# MGT.net
KiCad netlist of a schematic drawn in Altium Designer
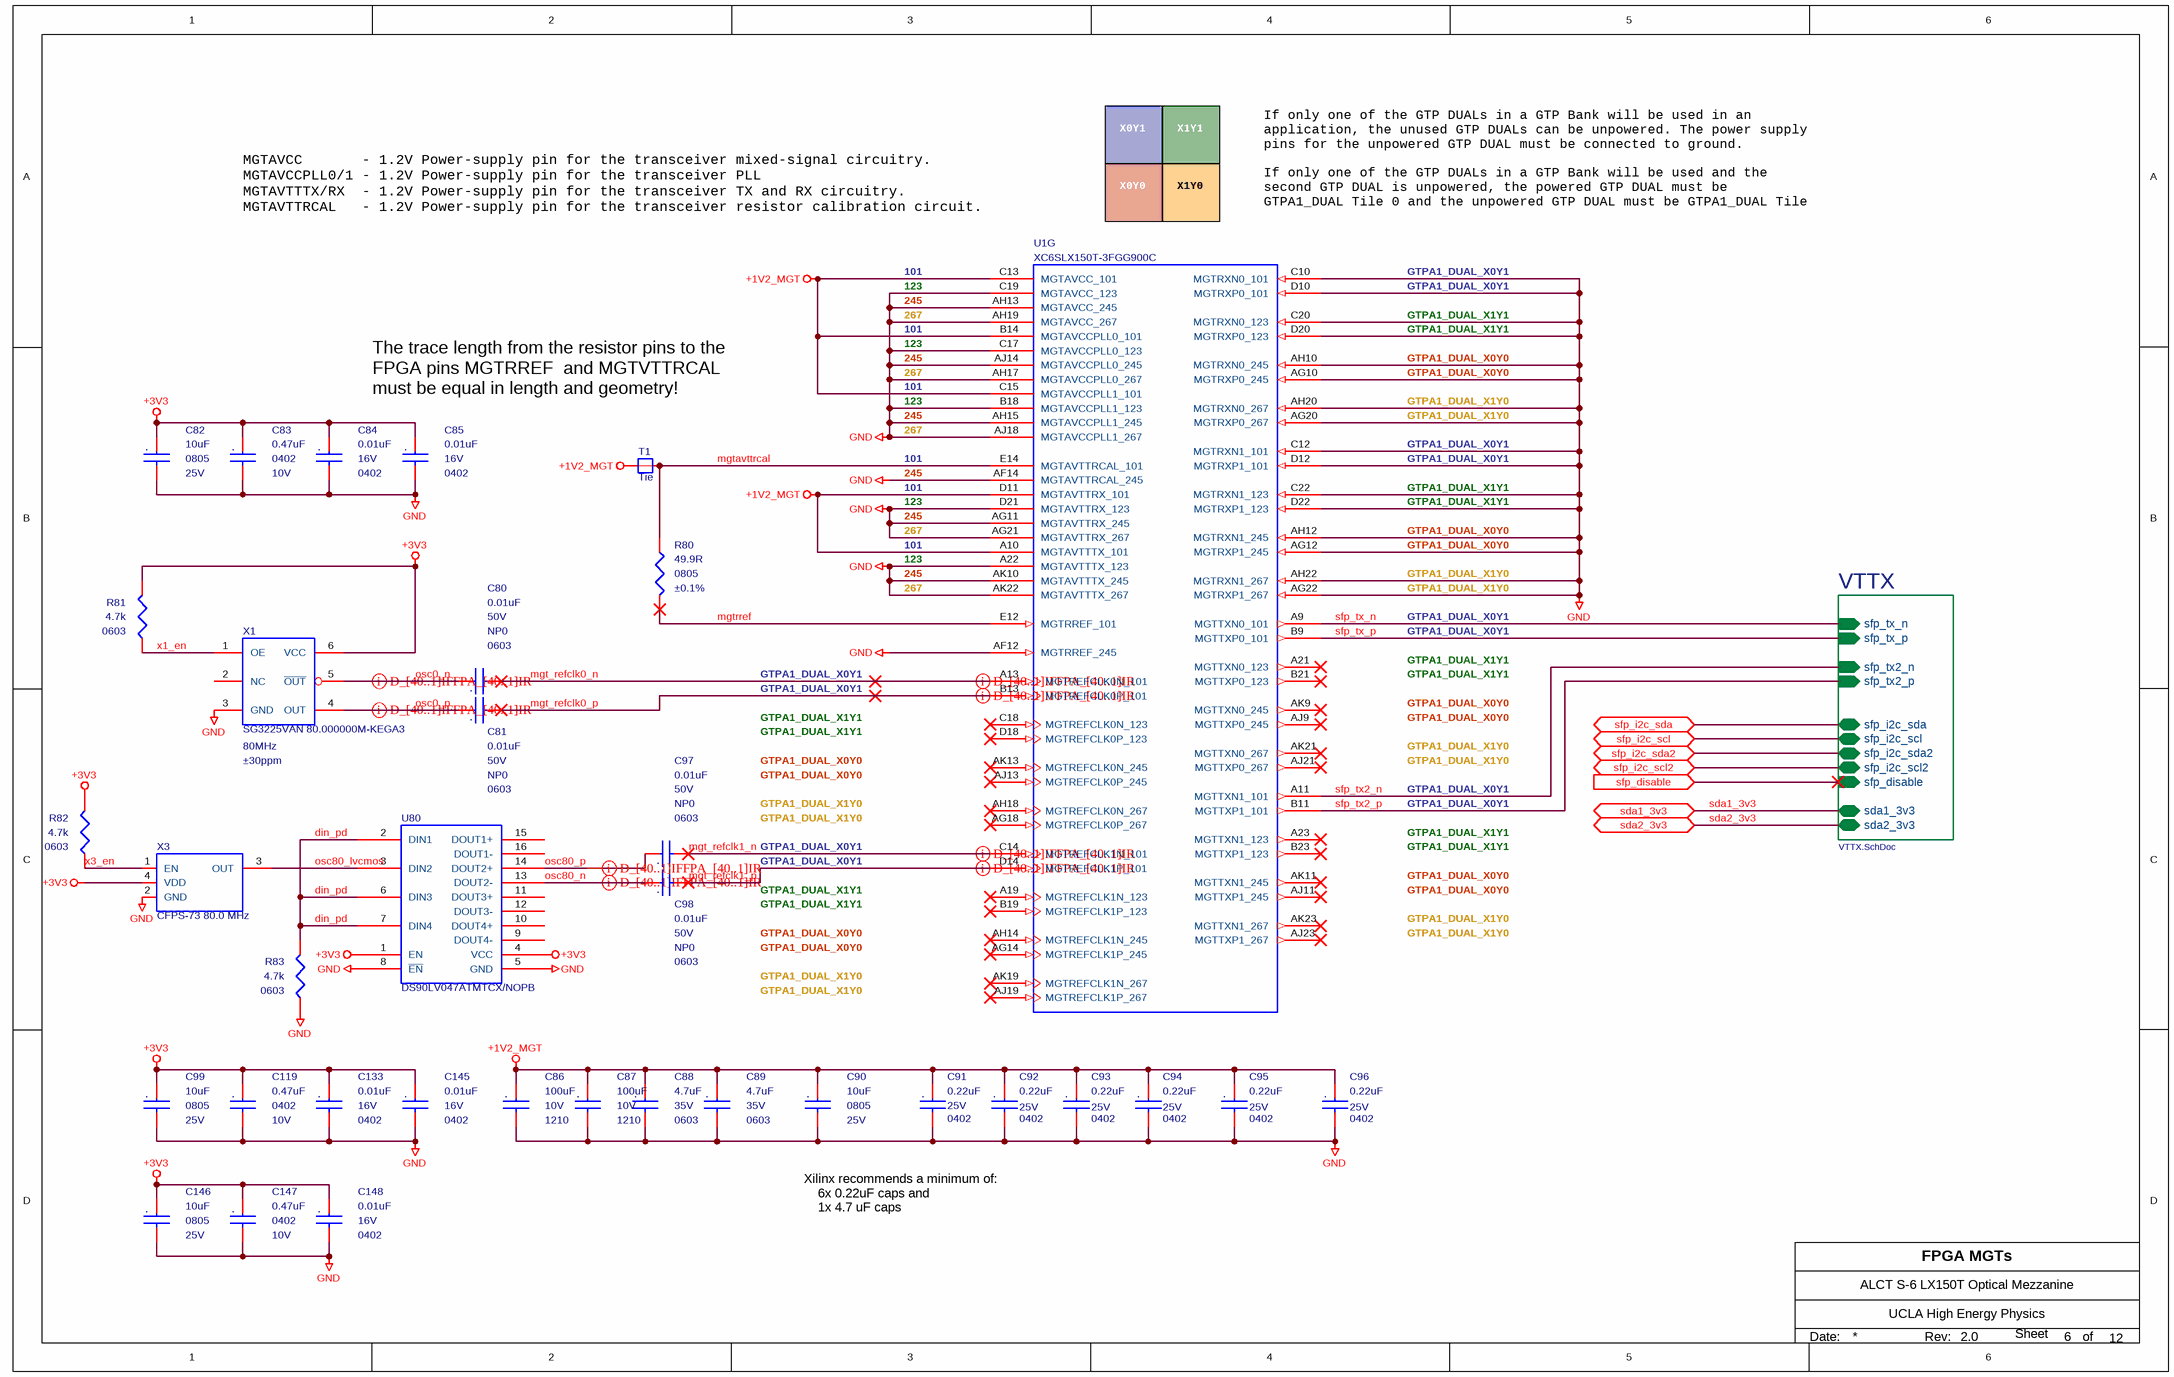
[diagram p0: MGT.SchDoc]

(export (version "E")
  (design (tool "Eeschema 10.0.6"))
  (components
    (comp (ref "C80")
      (value "0.01uF")
      (footprint "MC_S6/SM/C_0603_IPC")
      (description "CAP CER 10000PF 50V NP0 0603")
      (fields
        (field (name "MANUFACTURER") "KEMET")
        (field (name "MANUFACTURER PART NUMBER") "C0603C103J3GACTU")
        (field (name "TEMPERATURE COEFFICIENT") "NP0")
        (field (name "PACKAGE") "0603")
        (field (name "VOLTAGE - RATED") "50V")
      )
      (libsource (lib "ALCT_MEZ_SPARTAN6_Library") (part "C0603C103J3GACTU"))
    )
    (comp (ref "C81")
      (value "0.01uF")
      (footprint "MC_S6/SM/C_0603_IPC")
      (description "CAP CER 10000PF 50V NP0 0603")
      (fields
        (field (name "MANUFACTURER") "KEMET")
        (field (name "MANUFACTURER PART NUMBER") "C0603C103J3GACTU")
        (field (name "TEMPERATURE COEFFICIENT") "NP0")
        (field (name "PACKAGE") "0603")
        (field (name "VOLTAGE - RATED") "50V")
      )
      (libsource (lib "ALCT_MEZ_SPARTAN6_Library") (part "C0603C103J3GACTU"))
    )
    (comp (ref "C82")
      (value "10uF")
      (footprint "MC_S6/SM/C_0805_IPC")
      (description "CAP CER 10UF 25V X5R 0805")
      (fields
        (field (name "MANUFACTURER") "Murata Electronics North America")
        (field (name "MANUFACTURER PART NUMBER") "GRM21BR61E106KA73L")
        (field (name "VOLTAGE - RATED") "25V")
        (field (name "PACKAGE") "0805")
      )
      (libsource (lib "ALCT_MEZ_SPARTAN6_Library") (part "GRM21BR61E106KA73L"))
    )
    (comp (ref "C83")
      (value "0.47uF")
      (footprint "MC_S6/SM/C_0402_IPC")
      (description "CAP CER 0.47UF 10V X5R 0402")
      (fields
        (field (name "MANUFACTURER") "Murata Electronics North America")
        (field (name "MANUFACTURER PART NUMBER") "GRM155R61A474KE15J")
        (field (name "VOLTAGE - RATED") "10V")
        (field (name "PACKAGE") "0402")
      )
      (libsource (lib "ALCT_MEZ_SPARTAN6_Library") (part "GRM155R61A474KE15J"))
    )
    (comp (ref "C84")
      (value "0.01uF")
      (footprint "MC_S6/SM/C_0402_IPC")
      (description "CAP CER 10nF 16V X7R 0402")
      (fields
        (field (name "MANUFACTURER") "KEMET")
        (field (name "MANUFACTURER PART NUMBER") "C0402C103K4RACTU")
        (field (name "VOLTAGE - RATED") "16V")
        (field (name "PACKAGE") "0402")
      )
      (libsource (lib "ALCT_MEZ_SPARTAN6_Library") (part "C0402C103K4RACTU"))
    )
    (comp (ref "C85")
      (value "0.01uF")
      (footprint "MC_S6/SM/C_0402_IPC")
      (description "CAP CER 10nF 16V X7R 0402")
      (fields
        (field (name "MANUFACTURER") "KEMET")
        (field (name "MANUFACTURER PART NUMBER") "C0402C103K4RACTU")
        (field (name "VOLTAGE - RATED") "16V")
        (field (name "PACKAGE") "0402")
      )
      (libsource (lib "ALCT_MEZ_SPARTAN6_Library") (part "C0402C103K4RACTU"))
    )
    (comp (ref "C86")
      (value "100uF")
      (footprint "MC_S6/SM/C_1210_IPC")
      (description "CAP CER 100UF 10V X5R 1210")
      (fields
        (field (name "MANUFACTURER") "Taiyo Yuden")
        (field (name "MANUFACTURER PART NUMBER") "LMK325BJ107MM-T")
        (field (name "VOLTAGE - RATED") "10V")
        (field (name "PACKAGE") "1210")
      )
      (libsource (lib "ALCT_MEZ_SPARTAN6_Library") (part "LMK325BJ107MM-T"))
    )
    (comp (ref "C87")
      (value "100uF")
      (footprint "MC_S6/SM/C_1210_IPC")
      (description "CAP CER 100UF 10V X5R 1210")
      (fields
        (field (name "MANUFACTURER") "Taiyo Yuden")
        (field (name "MANUFACTURER PART NUMBER") "LMK325BJ107MM-T")
        (field (name "VOLTAGE - RATED") "10V")
        (field (name "PACKAGE") "1210")
      )
      (libsource (lib "ALCT_MEZ_SPARTAN6_Library") (part "LMK325BJ107MM-T"))
    )
    (comp (ref "C88")
      (value "4.7uF")
      (footprint "MC_S6/SM/C_0603_IPC")
      (description "CAP CER 4.7UF 35V X5R 0603")
      (fields
        (field (name "MANUFACTURER") "Murata")
        (field (name "MANUFACTURER PART NUMBER") "GRM188R6YA475KE15D")
        (field (name "VOLTAGE - RATED") "35V")
        (field (name "PACKAGE") "0603")
      )
      (libsource (lib "ALCT_MEZ_SPARTAN6_Library") (part "GRM188R6YA475KE15D"))
    )
    (comp (ref "C89")
      (value "4.7uF")
      (footprint "MC_S6/SM/C_0603_IPC")
      (description "CAP CER 4.7UF 35V X5R 0603")
      (fields
        (field (name "MANUFACTURER") "Murata")
        (field (name "MANUFACTURER PART NUMBER") "GRM188R6YA475KE15D")
        (field (name "VOLTAGE - RATED") "35V")
        (field (name "PACKAGE") "0603")
      )
      (libsource (lib "ALCT_MEZ_SPARTAN6_Library") (part "GRM188R6YA475KE15D"))
    )
    (comp (ref "C90")
      (value "10uF")
      (footprint "MC_S6/SM/C_0805_IPC")
      (description "CAP CER 10UF 25V X5R 0805")
      (fields
        (field (name "MANUFACTURER") "Murata Electronics North America")
        (field (name "MANUFACTURER PART NUMBER") "GRM21BR61E106KA73L")
        (field (name "VOLTAGE - RATED") "25V")
        (field (name "PACKAGE") "0805")
      )
      (libsource (lib "ALCT_MEZ_SPARTAN6_Library") (part "GRM21BR61E106KA73L"))
    )
    (comp (ref "C91")
      (value "0.22uF")
      (footprint "MC_S6/SM/C_0402_IPC")
      (description "CAP CER 0.22UF 15V X7R 0402")
      (fields
        (field (name "MANUFACTURER") "Murata Electronics North America")
        (field (name "MANUFACTURER PART NUMBER") "GRM155R71C224KA12D")
        (field (name "VOLTAGE - RATED") "25V")
        (field (name "PACKAGE") "0402")
      )
      (libsource (lib "ALCT_MEZ_SPARTAN6_Library") (part "GRM155R71C224KA12D"))
    )
    (comp (ref "C92")
      (value "0.22uF")
      (footprint "MC_S6/SM/C_0402_IPC")
      (description "CAP CER 0.22UF 15V X7R 0402")
      (fields
        (field (name "MANUFACTURER") "Murata Electronics North America")
        (field (name "MANUFACTURER PART NUMBER") "GRM155R71C224KA12D")
        (field (name "VOLTAGE - RATED") "25V")
        (field (name "PACKAGE") "0402")
      )
      (libsource (lib "ALCT_MEZ_SPARTAN6_Library") (part "GRM155R71C224KA12D"))
    )
    (comp (ref "C93")
      (value "0.22uF")
      (footprint "MC_S6/SM/C_0402_IPC")
      (description "CAP CER 0.22UF 15V X7R 0402")
      (fields
        (field (name "MANUFACTURER") "Murata Electronics North America")
        (field (name "MANUFACTURER PART NUMBER") "GRM155R71C224KA12D")
        (field (name "VOLTAGE - RATED") "25V")
        (field (name "PACKAGE") "0402")
      )
      (libsource (lib "ALCT_MEZ_SPARTAN6_Library") (part "GRM155R71C224KA12D"))
    )
    (comp (ref "C94")
      (value "0.22uF")
      (footprint "MC_S6/SM/C_0402_IPC")
      (description "CAP CER 0.22UF 15V X7R 0402")
      (fields
        (field (name "MANUFACTURER") "Murata Electronics North America")
        (field (name "MANUFACTURER PART NUMBER") "GRM155R71C224KA12D")
        (field (name "VOLTAGE - RATED") "25V")
        (field (name "PACKAGE") "0402")
      )
      (libsource (lib "ALCT_MEZ_SPARTAN6_Library") (part "GRM155R71C224KA12D"))
    )
    (comp (ref "C95")
      (value "0.22uF")
      (footprint "MC_S6/SM/C_0402_IPC")
      (description "CAP CER 0.22UF 15V X7R 0402")
      (fields
        (field (name "MANUFACTURER") "Murata Electronics North America")
        (field (name "MANUFACTURER PART NUMBER") "GRM155R71C224KA12D")
        (field (name "VOLTAGE - RATED") "25V")
        (field (name "PACKAGE") "0402")
      )
      (libsource (lib "ALCT_MEZ_SPARTAN6_Library") (part "GRM155R71C224KA12D"))
    )
    (comp (ref "C96")
      (value "0.22uF")
      (footprint "MC_S6/SM/C_0402_IPC")
      (description "CAP CER 0.22UF 15V X7R 0402")
      (fields
        (field (name "MANUFACTURER") "Murata Electronics North America")
        (field (name "MANUFACTURER PART NUMBER") "GRM155R71C224KA12D")
        (field (name "VOLTAGE - RATED") "25V")
        (field (name "PACKAGE") "0402")
      )
      (libsource (lib "ALCT_MEZ_SPARTAN6_Library") (part "GRM155R71C224KA12D"))
    )
    (comp (ref "C97")
      (value "0.01uF")
      (footprint "MC_S6/SM/C_0603_IPC")
      (description "CAP CER 10000PF 50V NP0 0603")
      (fields
        (field (name "MANUFACTURER") "KEMET")
        (field (name "MANUFACTURER PART NUMBER") "C0603C103J3GACTU")
        (field (name "TEMPERATURE COEFFICIENT") "NP0")
        (field (name "PACKAGE") "0603")
        (field (name "VOLTAGE - RATED") "50V")
      )
      (libsource (lib "ALCT_MEZ_SPARTAN6_Library") (part "C0603C103J3GACTU"))
    )
    (comp (ref "C98")
      (value "0.01uF")
      (footprint "MC_S6/SM/C_0603_IPC")
      (description "CAP CER 10000PF 50V NP0 0603")
      (fields
        (field (name "MANUFACTURER") "KEMET")
        (field (name "MANUFACTURER PART NUMBER") "C0603C103J3GACTU")
        (field (name "TEMPERATURE COEFFICIENT") "NP0")
        (field (name "PACKAGE") "0603")
        (field (name "VOLTAGE - RATED") "50V")
      )
      (libsource (lib "ALCT_MEZ_SPARTAN6_Library") (part "C0603C103J3GACTU"))
    )
    (comp (ref "C99")
      (value "10uF")
      (footprint "MC_S6/SM/C_0805_IPC")
      (description "CAP CER 10UF 25V X5R 0805")
      (fields
        (field (name "MANUFACTURER") "Murata Electronics North America")
        (field (name "MANUFACTURER PART NUMBER") "GRM21BR61E106KA73L")
        (field (name "VOLTAGE - RATED") "25V")
        (field (name "PACKAGE") "0805")
      )
      (libsource (lib "ALCT_MEZ_SPARTAN6_Library") (part "GRM21BR61E106KA73L"))
    )
    (comp (ref "C119")
      (value "0.47uF")
      (footprint "MC_S6/SM/C_0402_IPC")
      (description "CAP CER 0.47UF 10V X5R 0402")
      (fields
        (field (name "MANUFACTURER") "Murata Electronics North America")
        (field (name "MANUFACTURER PART NUMBER") "GRM155R61A474KE15J")
        (field (name "VOLTAGE - RATED") "10V")
        (field (name "PACKAGE") "0402")
      )
      (libsource (lib "ALCT_MEZ_SPARTAN6_Library") (part "GRM155R61A474KE15J"))
    )
    (comp (ref "C133")
      (value "0.01uF")
      (footprint "MC_S6/SM/C_0402_IPC")
      (description "CAP CER 10nF 16V X7R 0402")
      (fields
        (field (name "MANUFACTURER") "KEMET")
        (field (name "MANUFACTURER PART NUMBER") "C0402C103K4RACTU")
        (field (name "VOLTAGE - RATED") "16V")
        (field (name "PACKAGE") "0402")
      )
      (libsource (lib "ALCT_MEZ_SPARTAN6_Library") (part "C0402C103K4RACTU"))
    )
    (comp (ref "C145")
      (value "0.01uF")
      (footprint "MC_S6/SM/C_0402_IPC")
      (description "CAP CER 10nF 16V X7R 0402")
      (fields
        (field (name "MANUFACTURER") "KEMET")
        (field (name "MANUFACTURER PART NUMBER") "C0402C103K4RACTU")
        (field (name "VOLTAGE - RATED") "16V")
        (field (name "PACKAGE") "0402")
      )
      (libsource (lib "ALCT_MEZ_SPARTAN6_Library") (part "C0402C103K4RACTU"))
    )
    (comp (ref "C146")
      (value "10uF")
      (footprint "MC_S6/SM/C_0805_IPC")
      (description "CAP CER 10UF 25V X5R 0805")
      (fields
        (field (name "MANUFACTURER") "Murata Electronics North America")
        (field (name "MANUFACTURER PART NUMBER") "GRM21BR61E106KA73L")
        (field (name "VOLTAGE - RATED") "25V")
        (field (name "PACKAGE") "0805")
      )
      (libsource (lib "ALCT_MEZ_SPARTAN6_Library") (part "GRM21BR61E106KA73L"))
    )
    (comp (ref "C147")
      (value "0.47uF")
      (footprint "MC_S6/SM/C_0402_IPC")
      (description "CAP CER 0.47UF 10V X5R 0402")
      (fields
        (field (name "MANUFACTURER") "Murata Electronics North America")
        (field (name "MANUFACTURER PART NUMBER") "GRM155R61A474KE15J")
        (field (name "VOLTAGE - RATED") "10V")
        (field (name "PACKAGE") "0402")
      )
      (libsource (lib "ALCT_MEZ_SPARTAN6_Library") (part "GRM155R61A474KE15J"))
    )
    (comp (ref "C148")
      (value "0.01uF")
      (footprint "MC_S6/SM/C_0402_IPC")
      (description "CAP CER 10nF 16V X7R 0402")
      (fields
        (field (name "MANUFACTURER") "KEMET")
        (field (name "MANUFACTURER PART NUMBER") "C0402C103K4RACTU")
        (field (name "VOLTAGE - RATED") "16V")
        (field (name "PACKAGE") "0402")
      )
      (libsource (lib "ALCT_MEZ_SPARTAN6_Library") (part "C0402C103K4RACTU"))
    )
    (comp (ref "R80")
      (value "49.9R")
      (footprint "MC_S6/SM/R_0805_IPC")
      (description "RES SMD 49.9 OHM 0.1% 1/8W 0805")
      (fields
        (field (name "MANUFACTURER") "Panasonic Electronic Components")
        (field (name "MANUFACTURER PART NUMBER") "ERA-6AEB49R9V")
        (field (name "TOLERANCE") "±0.1%")
        (field (name "SUPPLIER DEVICE PACKAGE") "0805")
      )
      (libsource (lib "ALCT_MEZ_SPARTAN6_Library") (part "ERA-6AEB49R9V"))
    )
    (comp (ref "R81")
      (value "4.7k")
      (footprint "MC_S6/SM/R_0603_IPC")
      (description "RES SMD 4.7K OHM 1% 1/10W 0603")
      (fields
        (field (name "MANUFACTURER") "Bourns Inc.")
        (field (name "MANUFACTURER PART NUMBER") "CR0603-FX-4701ELF")
        (field (name "SUPPLIER DEVICE PACKAGE") "0603")
      )
      (libsource (lib "ALCT_MEZ_SPARTAN6_Library") (part "CR0603-FX-4701ELF"))
    )
    (comp (ref "R82")
      (value "4.7k")
      (footprint "MC_S6/SM/R_0603_IPC")
      (description "RES SMD 4.7K OHM 1% 1/10W 0603")
      (fields
        (field (name "MANUFACTURER") "Bourns Inc.")
        (field (name "MANUFACTURER PART NUMBER") "CR0603-FX-4701ELF")
        (field (name "SUPPLIER DEVICE PACKAGE") "0603")
      )
      (libsource (lib "ALCT_MEZ_SPARTAN6_Library") (part "CR0603-FX-4701ELF"))
    )
    (comp (ref "R83")
      (value "4.7k")
      (footprint "MC_S6/SM/R_0603_IPC")
      (description "RES SMD 4.7K OHM 1% 1/10W 0603")
      (fields
        (field (name "MANUFACTURER") "Bourns Inc.")
        (field (name "MANUFACTURER PART NUMBER") "CR0603-FX-4701ELF")
        (field (name "SUPPLIER DEVICE PACKAGE") "0603")
      )
      (libsource (lib "ALCT_MEZ_SPARTAN6_Library") (part "CR0603-FX-4701ELF"))
    )
    (comp (ref "T1")
      (value "Tie")
      (footprint "MC_S6/TH/TIE_VIA")
      (libsource (lib "ALCT_MEZ_SPARTAN6_Library") (part "NET TIE VIA"))
    )
    (comp (ref "U1")
      (value "XC6SLX150T-3FGG900C")
      (footprint "MC_S6/BGA/FGG900")
      (fields (field (name "MANUFACTURER") "Xilinx Inc."))
      (libsource (lib "ALCT_MEZ_SPARTAN6_Library") (part "XC6SLX150T-3FGG900C"))
    )
    (comp (ref "U80")
      (value "DS90LV047ATMTCX/NOPB")
      (footprint "MC_S6/SM/TSSOP16")
      (description "LVDS Driver 0.45V 16-Pin TSSOP T/R")
      (fields (field (name "MANUFACTURER") "TI National Semiconductor"))
      (libsource (lib "ALCT_MEZ_SPARTAN6_Library") (part "DS90LV047ATMTCX"))
    )
    (comp (ref "X1")
      (value "SG3225VAN 80.000000M-KEGA3")
      (footprint "MC_S6/SM/XTAL-LVDS-3.2-2.5")
      (description "OSC 80.0000MHZ LVDS SMD")
      (fields
        (field (name "MANUFACTURER") "EPSON")
        (field (name "FREQUENCY") "80MHz")
        (field (name "FREQUENCY STABILITY") "±30ppm")
      )
      (libsource (lib "ALCT_MEZ_SPARTAN6_Library") (part "SG3225VAN 80.000000M-KEGA3"))
    )
    (comp (ref "X3")
      (value "CFPS-73 80.0 MHz")
      (footprint "MC_S6/SM/XTAL-7x5.08")
      (description "XTAL, 80MHz, CMOS")
      (fields
        (field (name "MANUFACTURER") "IQD")
        (field (name "MANUFACTURER PART NUMBER") "LFSPXO009441REEL")
      )
      (libsource (lib "ALCT_MEZ_SPARTAN6_Library") (part "LFSPXO009441"))
    )
  )
  (nets
    (net (code "1") (name "+1V2_MGT") (class "Default")
      (node (ref "C86") (pin "1") (pinfunction "1_1") (pintype "passive"))
      (node (ref "C87") (pin "1") (pinfunction "1_1") (pintype "passive"))
      (node (ref "C88") (pin "1") (pinfunction "1_1") (pintype "passive"))
      (node (ref "C89") (pin "1") (pinfunction "1_1") (pintype "passive"))
      (node (ref "C90") (pin "1") (pinfunction "1_1") (pintype "passive"))
      (node (ref "C91") (pin "1") (pinfunction "1_1") (pintype "passive"))
      (node (ref "C92") (pin "1") (pinfunction "1_1") (pintype "passive"))
      (node (ref "C93") (pin "1") (pinfunction "1_1") (pintype "passive"))
      (node (ref "C94") (pin "1") (pinfunction "1_1") (pintype "passive"))
      (node (ref "C95") (pin "1") (pinfunction "1_1") (pintype "passive"))
      (node (ref "C96") (pin "1") (pinfunction "1_1") (pintype "passive"))
      (node (ref "T1") (pin "2") (pinfunction "2_2") (pintype "passive"))
      (node (ref "U1") (pin "A10") (pinfunction "MGTAVTTTX_101_A10") (pintype "power_in"))
      (node (ref "U1") (pin "B14") (pinfunction "MGTAVCCPLL0_101_B14") (pintype "power_in"))
      (node (ref "U1") (pin "C13") (pinfunction "MGTAVCC_101_C13") (pintype "power_in"))
      (node (ref "U1") (pin "C15") (pinfunction "MGTAVCCPLL1_101_C15") (pintype "power_in"))
      (node (ref "U1") (pin "D11") (pinfunction "MGTAVTTRX_101_D11") (pintype "power_in"))
    )
    (net (code "2") (name "+3V3") (class "Default")
      (node (ref "C119") (pin "1") (pinfunction "1_1") (pintype "passive"))
      (node (ref "C133") (pin "1") (pinfunction "1_1") (pintype "passive"))
      (node (ref "C145") (pin "1") (pinfunction "1_1") (pintype "passive"))
      (node (ref "C146") (pin "1") (pinfunction "1_1") (pintype "passive"))
      (node (ref "C147") (pin "1") (pinfunction "1_1") (pintype "passive"))
      (node (ref "C148") (pin "1") (pinfunction "1_1") (pintype "passive"))
      (node (ref "C82") (pin "1") (pinfunction "1_1") (pintype "passive"))
      (node (ref "C83") (pin "1") (pinfunction "1_1") (pintype "passive"))
      (node (ref "C84") (pin "1") (pinfunction "1_1") (pintype "passive"))
      (node (ref "C85") (pin "1") (pinfunction "1_1") (pintype "passive"))
      (node (ref "C99") (pin "1") (pinfunction "1_1") (pintype "passive"))
      (node (ref "R81") (pin "1") (pinfunction "1_1") (pintype "passive"))
      (node (ref "R82") (pin "1") (pinfunction "1_1") (pintype "passive"))
      (node (ref "U80") (pin "1") (pinfunction "EN_1") (pintype "power_in"))
      (node (ref "U80") (pin "4") (pinfunction "VCC_4") (pintype "power_in"))
      (node (ref "X1") (pin "6") (pinfunction "VCC_6") (pintype "passive"))
      (node (ref "X3") (pin "4") (pinfunction "VDD_4") (pintype "passive"))
    )
    (net (code "3") (name "/din_pd") (class "Default")
      (node (ref "R83") (pin "1") (pinfunction "1_1") (pintype "passive"))
      (node (ref "U80") (pin "2") (pinfunction "DIN1_2") (pintype "power_in"))
      (node (ref "U80") (pin "6") (pinfunction "DIN3_6") (pintype "power_in"))
      (node (ref "U80") (pin "7") (pinfunction "DIN4_7") (pintype "power_in"))
    )
    (net (code "4") (name "/mgt_refclk0_n") (class "Default")
      (node (ref "C80") (pin "2") (pinfunction "2_2") (pintype "passive"))
      (node (ref "U1") (pin "A13") (pinfunction "MGTREFCLK0N_101_A13") (pintype "input"))
    )
    (net (code "5") (name "/mgt_refclk0_p") (class "Default")
      (node (ref "C81") (pin "2") (pinfunction "2_2") (pintype "passive"))
      (node (ref "U1") (pin "B13") (pinfunction "MGTREFCLK0P_101_B13") (pintype "input"))
    )
    (net (code "6") (name "/mgt_refclk1_n") (class "Default")
      (node (ref "C97") (pin "2") (pinfunction "2_2") (pintype "passive"))
      (node (ref "U1") (pin "C14") (pinfunction "MGTREFCLK1N_101_C14") (pintype "input"))
    )
    (net (code "7") (name "/mgt_refclk1_p") (class "Default")
      (node (ref "C98") (pin "2") (pinfunction "2_2") (pintype "passive"))
      (node (ref "U1") (pin "D14") (pinfunction "MGTREFCLK1P_101_D14") (pintype "input"))
    )
    (net (code "8") (name "/mgtavttrcal") (class "Default")
      (node (ref "R80") (pin "1") (pinfunction "1_1") (pintype "passive"))
      (node (ref "T1") (pin "1") (pinfunction "1_1") (pintype "passive"))
      (node (ref "U1") (pin "E14") (pinfunction "MGTAVTTRCAL_101_E14") (pintype "power_in"))
    )
    (net (code "9") (name "/mgtrref") (class "Default")
      (node (ref "R80") (pin "2") (pinfunction "2_2") (pintype "passive"))
      (node (ref "U1") (pin "E12") (pinfunction "MGTRREF_101_E12") (pintype "input"))
    )
    (net (code "10") (name "/osc0_n") (class "Default")
      (node (ref "C80") (pin "1") (pinfunction "1_1") (pintype "passive"))
      (node (ref "X1") (pin "5") (pinfunction "~{OUT}_5") (pintype "passive"))
    )
    (net (code "11") (name "/osc0_p") (class "Default")
      (node (ref "C81") (pin "1") (pinfunction "1_1") (pintype "passive"))
      (node (ref "X1") (pin "4") (pinfunction "OUT_4") (pintype "passive"))
    )
    (net (code "12") (name "/osc80_lvcmos") (class "Default")
      (node (ref "U80") (pin "3") (pinfunction "DIN2_3") (pintype "power_in"))
      (node (ref "X3") (pin "3") (pinfunction "OUT_3") (pintype "passive"))
    )
    (net (code "13") (name "/osc80_n") (class "Default")
      (node (ref "C98") (pin "1") (pinfunction "1_1") (pintype "passive"))
      (node (ref "U80") (pin "13") (pinfunction "DOUT2-_13") (pintype "power_in"))
    )
    (net (code "14") (name "/osc80_p") (class "Default")
      (node (ref "C97") (pin "1") (pinfunction "1_1") (pintype "passive"))
      (node (ref "U80") (pin "14") (pinfunction "DOUT2+_14") (pintype "power_in"))
    )
    (net (code "22") (name "/sfp_tx2_n") (class "Default")
      (node (ref "U1") (pin "A11") (pinfunction "MGTTXN1_101_A11") (pintype "output"))
    )
    (net (code "23") (name "/sfp_tx2_p") (class "Default")
      (node (ref "U1") (pin "B11") (pinfunction "MGTTXP1_101_B11") (pintype "output"))
    )
    (net (code "24") (name "/sfp_tx_n") (class "Default")
      (node (ref "U1") (pin "A9") (pinfunction "MGTTXN0_101_A9") (pintype "output"))
    )
    (net (code "25") (name "/sfp_tx_p") (class "Default")
      (node (ref "U1") (pin "B9") (pinfunction "MGTTXP0_101_B9") (pintype "output"))
    )
    (net (code "26") (name "/x1_en") (class "Default")
      (node (ref "R81") (pin "2") (pinfunction "2_2") (pintype "passive"))
      (node (ref "X1") (pin "1") (pinfunction "OE_1") (pintype "passive"))
    )
    (net (code "27") (name "/x3_en") (class "Default")
      (node (ref "R82") (pin "2") (pinfunction "2_2") (pintype "passive"))
      (node (ref "X3") (pin "1") (pinfunction "EN_1") (pintype "passive"))
    )
    (net (code "28") (name "GND") (class "Default")
      (node (ref "C119") (pin "2") (pinfunction "2_2") (pintype "passive"))
      (node (ref "C133") (pin "2") (pinfunction "2_2") (pintype "passive"))
      (node (ref "C145") (pin "2") (pinfunction "2_2") (pintype "passive"))
      (node (ref "C146") (pin "2") (pinfunction "2_2") (pintype "passive"))
      (node (ref "C147") (pin "2") (pinfunction "2_2") (pintype "passive"))
      (node (ref "C148") (pin "2") (pinfunction "2_2") (pintype "passive"))
      (node (ref "C82") (pin "2") (pinfunction "2_2") (pintype "passive"))
      (node (ref "C83") (pin "2") (pinfunction "2_2") (pintype "passive"))
      (node (ref "C84") (pin "2") (pinfunction "2_2") (pintype "passive"))
      (node (ref "C85") (pin "2") (pinfunction "2_2") (pintype "passive"))
      (node (ref "C86") (pin "2") (pinfunction "2_2") (pintype "passive"))
      (node (ref "C87") (pin "2") (pinfunction "2_2") (pintype "passive"))
      (node (ref "C88") (pin "2") (pinfunction "2_2") (pintype "passive"))
      (node (ref "C89") (pin "2") (pinfunction "2_2") (pintype "passive"))
      (node (ref "C90") (pin "2") (pinfunction "2_2") (pintype "passive"))
      (node (ref "C91") (pin "2") (pinfunction "2_2") (pintype "passive"))
      (node (ref "C92") (pin "2") (pinfunction "2_2") (pintype "passive"))
      (node (ref "C93") (pin "2") (pinfunction "2_2") (pintype "passive"))
      (node (ref "C94") (pin "2") (pinfunction "2_2") (pintype "passive"))
      (node (ref "C95") (pin "2") (pinfunction "2_2") (pintype "passive"))
      (node (ref "C96") (pin "2") (pinfunction "2_2") (pintype "passive"))
      (node (ref "C99") (pin "2") (pinfunction "2_2") (pintype "passive"))
      (node (ref "R83") (pin "2") (pinfunction "2_2") (pintype "passive"))
      (node (ref "U1") (pin "A22") (pinfunction "MGTAVTTTX_123_A22") (pintype "power_in"))
      (node (ref "U1") (pin "AF12") (pinfunction "MGTRREF_245_AF12") (pintype "input"))
      (node (ref "U1") (pin "AF14") (pinfunction "MGTAVTTRCAL_245_AF14") (pintype "power_in"))
      (node (ref "U1") (pin "AG10") (pinfunction "MGTRXP0_245_AG10") (pintype "input"))
      (node (ref "U1") (pin "AG11") (pinfunction "MGTAVTTRX_245_AG11") (pintype "power_in"))
      (node (ref "U1") (pin "AG12") (pinfunction "MGTRXP1_245_AG12") (pintype "input"))
      (node (ref "U1") (pin "AG20") (pinfunction "MGTRXP0_267_AG20") (pintype "input"))
      (node (ref "U1") (pin "AG21") (pinfunction "MGTAVTTRX_267_AG21") (pintype "power_in"))
      (node (ref "U1") (pin "AG22") (pinfunction "MGTRXP1_267_AG22") (pintype "input"))
      (node (ref "U1") (pin "AH10") (pinfunction "MGTRXN0_245_AH10") (pintype "input"))
      (node (ref "U1") (pin "AH12") (pinfunction "MGTRXN1_245_AH12") (pintype "input"))
      (node (ref "U1") (pin "AH13") (pinfunction "MGTAVCC_245_AH13") (pintype "power_in"))
      (node (ref "U1") (pin "AH15") (pinfunction "MGTAVCCPLL1_245_AH15") (pintype "power_in"))
      (node (ref "U1") (pin "AH17") (pinfunction "MGTAVCCPLL0_267_AH17") (pintype "power_in"))
      (node (ref "U1") (pin "AH19") (pinfunction "MGTAVCC_267_AH19") (pintype "power_in"))
      (node (ref "U1") (pin "AH20") (pinfunction "MGTRXN0_267_AH20") (pintype "input"))
      (node (ref "U1") (pin "AH22") (pinfunction "MGTRXN1_267_AH22") (pintype "input"))
      (node (ref "U1") (pin "AJ14") (pinfunction "MGTAVCCPLL0_245_AJ14") (pintype "power_in"))
      (node (ref "U1") (pin "AJ18") (pinfunction "MGTAVCCPLL1_267_AJ18") (pintype "power_in"))
      (node (ref "U1") (pin "AK10") (pinfunction "MGTAVTTTX_245_AK10") (pintype "power_in"))
      (node (ref "U1") (pin "AK22") (pinfunction "MGTAVTTTX_267_AK22") (pintype "power_in"))
      (node (ref "U1") (pin "B18") (pinfunction "MGTAVCCPLL1_123_B18") (pintype "power_in"))
      (node (ref "U1") (pin "C10") (pinfunction "MGTRXN0_101_C10") (pintype "input"))
      (node (ref "U1") (pin "C12") (pinfunction "MGTRXN1_101_C12") (pintype "input"))
      (node (ref "U1") (pin "C17") (pinfunction "MGTAVCCPLL0_123_C17") (pintype "power_in"))
      (node (ref "U1") (pin "C19") (pinfunction "MGTAVCC_123_C19") (pintype "power_in"))
      (node (ref "U1") (pin "C20") (pinfunction "MGTRXN0_123_C20") (pintype "input"))
      (node (ref "U1") (pin "C22") (pinfunction "MGTRXN1_123_C22") (pintype "input"))
      (node (ref "U1") (pin "D10") (pinfunction "MGTRXP0_101_D10") (pintype "input"))
      (node (ref "U1") (pin "D12") (pinfunction "MGTRXP1_101_D12") (pintype "input"))
      (node (ref "U1") (pin "D20") (pinfunction "MGTRXP0_123_D20") (pintype "input"))
      (node (ref "U1") (pin "D21") (pinfunction "MGTAVTTRX_123_D21") (pintype "power_in"))
      (node (ref "U1") (pin "D22") (pinfunction "MGTRXP1_123_D22") (pintype "input"))
      (node (ref "U80") (pin "5") (pinfunction "GND_5") (pintype "power_in"))
      (node (ref "U80") (pin "8") (pinfunction "~{EN}_8") (pintype "power_in"))
      (node (ref "X1") (pin "3") (pinfunction "GND_3") (pintype "passive"))
      (node (ref "X3") (pin "2") (pinfunction "GND_2") (pintype "passive"))
    )
    (net (code "29") (name "unconnected-(U1G-MGTREFCLK0N_123-PadC18)") (class "Default")
      (node (ref "U1") (pin "C18") (pinfunction "MGTREFCLK0N_123_C18") (pintype "input+no_connect"))
    )
    (net (code "30") (name "unconnected-(U1G-MGTREFCLK0N_245-PadAK13)") (class "Default")
      (node (ref "U1") (pin "AK13") (pinfunction "MGTREFCLK0N_245_AK13") (pintype "input+no_connect"))
    )
    (net (code "31") (name "unconnected-(U1G-MGTREFCLK0N_267-PadAH18)") (class "Default")
      (node (ref "U1") (pin "AH18") (pinfunction "MGTREFCLK0N_267_AH18") (pintype "input+no_connect"))
    )
    (net (code "32") (name "unconnected-(U1G-MGTREFCLK0P_123-PadD18)") (class "Default")
      (node (ref "U1") (pin "D18") (pinfunction "MGTREFCLK0P_123_D18") (pintype "input+no_connect"))
    )
    (net (code "33") (name "unconnected-(U1G-MGTREFCLK0P_245-PadAJ13)") (class "Default")
      (node (ref "U1") (pin "AJ13") (pinfunction "MGTREFCLK0P_245_AJ13") (pintype "input+no_connect"))
    )
    (net (code "34") (name "unconnected-(U1G-MGTREFCLK0P_267-PadAG18)") (class "Default")
      (node (ref "U1") (pin "AG18") (pinfunction "MGTREFCLK0P_267_AG18") (pintype "input+no_connect"))
    )
    (net (code "35") (name "unconnected-(U1G-MGTREFCLK1N_123-PadA19)") (class "Default")
      (node (ref "U1") (pin "A19") (pinfunction "MGTREFCLK1N_123_A19") (pintype "input+no_connect"))
    )
    (net (code "36") (name "unconnected-(U1G-MGTREFCLK1N_245-PadAH14)") (class "Default")
      (node (ref "U1") (pin "AH14") (pinfunction "MGTREFCLK1N_245_AH14") (pintype "input+no_connect"))
    )
    (net (code "37") (name "unconnected-(U1G-MGTREFCLK1N_267-PadAK19)") (class "Default")
      (node (ref "U1") (pin "AK19") (pinfunction "MGTREFCLK1N_267_AK19") (pintype "input+no_connect"))
    )
    (net (code "38") (name "unconnected-(U1G-MGTREFCLK1P_123-PadB19)") (class "Default")
      (node (ref "U1") (pin "B19") (pinfunction "MGTREFCLK1P_123_B19") (pintype "input+no_connect"))
    )
    (net (code "39") (name "unconnected-(U1G-MGTREFCLK1P_245-PadAG14)") (class "Default")
      (node (ref "U1") (pin "AG14") (pinfunction "MGTREFCLK1P_245_AG14") (pintype "input+no_connect"))
    )
    (net (code "40") (name "unconnected-(U1G-MGTREFCLK1P_267-PadAJ19)") (class "Default")
      (node (ref "U1") (pin "AJ19") (pinfunction "MGTREFCLK1P_267_AJ19") (pintype "input+no_connect"))
    )
    (net (code "41") (name "unconnected-(U1G-MGTTXN0_123-PadA21)") (class "Default")
      (node (ref "U1") (pin "A21") (pinfunction "MGTTXN0_123_A21") (pintype "output+no_connect"))
    )
    (net (code "42") (name "unconnected-(U1G-MGTTXN0_245-PadAK9)") (class "Default")
      (node (ref "U1") (pin "AK9") (pinfunction "MGTTXN0_245_AK9") (pintype "output+no_connect"))
    )
    (net (code "43") (name "unconnected-(U1G-MGTTXN0_267-PadAK21)") (class "Default")
      (node (ref "U1") (pin "AK21") (pinfunction "MGTTXN0_267_AK21") (pintype "output+no_connect"))
    )
    (net (code "44") (name "unconnected-(U1G-MGTTXN1_123-PadA23)") (class "Default")
      (node (ref "U1") (pin "A23") (pinfunction "MGTTXN1_123_A23") (pintype "output+no_connect"))
    )
    (net (code "45") (name "unconnected-(U1G-MGTTXN1_245-PadAK11)") (class "Default")
      (node (ref "U1") (pin "AK11") (pinfunction "MGTTXN1_245_AK11") (pintype "output+no_connect"))
    )
    (net (code "46") (name "unconnected-(U1G-MGTTXN1_267-PadAK23)") (class "Default")
      (node (ref "U1") (pin "AK23") (pinfunction "MGTTXN1_267_AK23") (pintype "output+no_connect"))
    )
    (net (code "47") (name "unconnected-(U1G-MGTTXP0_123-PadB21)") (class "Default")
      (node (ref "U1") (pin "B21") (pinfunction "MGTTXP0_123_B21") (pintype "output+no_connect"))
    )
    (net (code "48") (name "unconnected-(U1G-MGTTXP0_245-PadAJ9)") (class "Default")
      (node (ref "U1") (pin "AJ9") (pinfunction "MGTTXP0_245_AJ9") (pintype "output+no_connect"))
    )
    (net (code "49") (name "unconnected-(U1G-MGTTXP0_267-PadAJ21)") (class "Default")
      (node (ref "U1") (pin "AJ21") (pinfunction "MGTTXP0_267_AJ21") (pintype "output+no_connect"))
    )
    (net (code "50") (name "unconnected-(U1G-MGTTXP1_123-PadB23)") (class "Default")
      (node (ref "U1") (pin "B23") (pinfunction "MGTTXP1_123_B23") (pintype "output+no_connect"))
    )
    (net (code "51") (name "unconnected-(U1G-MGTTXP1_245-PadAJ11)") (class "Default")
      (node (ref "U1") (pin "AJ11") (pinfunction "MGTTXP1_245_AJ11") (pintype "output+no_connect"))
    )
    (net (code "52") (name "unconnected-(U1G-MGTTXP1_267-PadAJ23)") (class "Default")
      (node (ref "U1") (pin "AJ23") (pinfunction "MGTTXP1_267_AJ23") (pintype "output+no_connect"))
    )
    (net (code "53") (name "unconnected-(U80-DOUT1+-Pad15)") (class "Default")
      (node (ref "U80") (pin "15") (pinfunction "DOUT1+_15") (pintype "power_in"))
    )
    (net (code "54") (name "unconnected-(U80-DOUT1--Pad16)") (class "Default")
      (node (ref "U80") (pin "16") (pinfunction "DOUT1-_16") (pintype "power_in"))
    )
    (net (code "55") (name "unconnected-(U80-DOUT3+-Pad11)") (class "Default")
      (node (ref "U80") (pin "11") (pinfunction "DOUT3+_11") (pintype "power_in"))
    )
    (net (code "56") (name "unconnected-(U80-DOUT3--Pad12)") (class "Default")
      (node (ref "U80") (pin "12") (pinfunction "DOUT3-_12") (pintype "power_in"))
    )
    (net (code "57") (name "unconnected-(U80-DOUT4+-Pad10)") (class "Default")
      (node (ref "U80") (pin "10") (pinfunction "DOUT4+_10") (pintype "power_in"))
    )
    (net (code "58") (name "unconnected-(U80-DOUT4--Pad9)") (class "Default")
      (node (ref "U80") (pin "9") (pinfunction "DOUT4-_9") (pintype "power_in"))
    )
    (net (code "59") (name "unconnected-(X1-NC-Pad2)") (class "Default")
      (node (ref "X1") (pin "2") (pinfunction "NC_2") (pintype "passive"))
    )
  )
)
